# FT2232H.net
KiCad netlist of a schematic drawn in Altium Designer
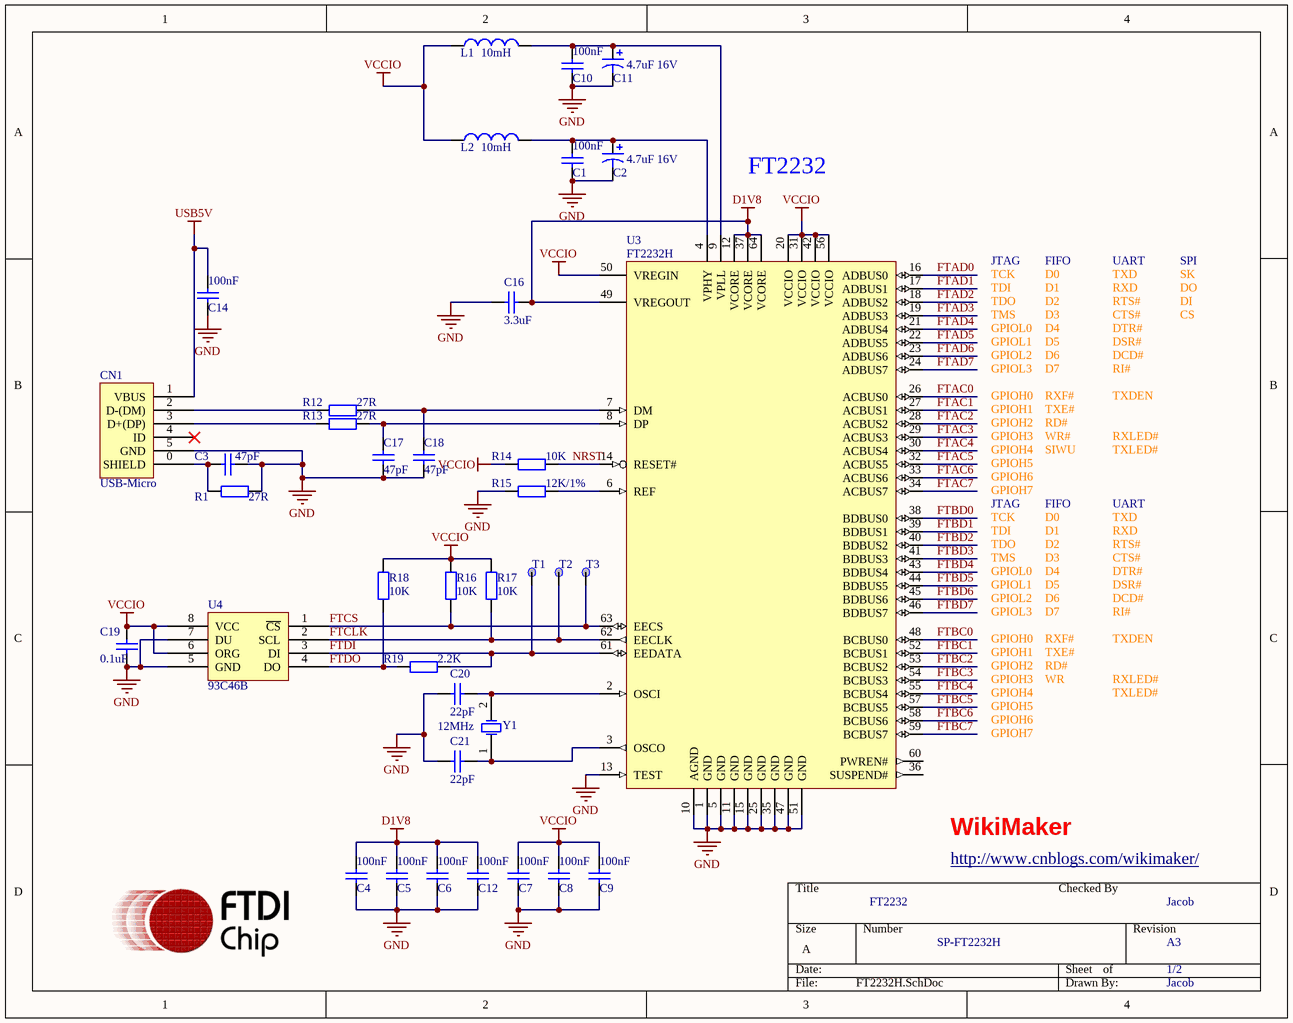
[diagram p0: FT2232H.SchDoc]

(export (version "E")
  (design (tool "Eeschema 10.0.6"))
  (components
    (comp (ref "C1")
      (value "100nF")
      (footprint "0603M")
      (description "Capacitor")
      (fields (field (name "PUBLISHER") "Altium Limited"))
      (libsource (lib "Miscellaneous Devices") (part "Cap"))
    )
    (comp (ref "C2")
      (value "4.7uF 16V")
      (footprint "0805M")
      (description "Polarized Capacitor (Radial)")
      (fields (field (name "PUBLISHER") "Altium Limited"))
      (libsource (lib "Miscellaneous Devices") (part "Cap Pol1"))
    )
    (comp (ref "C3")
      (value "47pF")
      (footprint "0603M")
      (description "Capacitor")
      (fields (field (name "PUBLISHER") "Altium Limited"))
      (libsource (lib "Miscellaneous Devices") (part "Cap"))
    )
    (comp (ref "C4")
      (value "100nF")
      (footprint "0603M")
      (description "Capacitor")
      (fields (field (name "PUBLISHER") "Altium Limited"))
      (libsource (lib "Miscellaneous Devices") (part "Cap"))
    )
    (comp (ref "C5")
      (value "100nF")
      (footprint "0603M")
      (description "Capacitor")
      (fields (field (name "PUBLISHER") "Altium Limited"))
      (libsource (lib "Miscellaneous Devices") (part "Cap"))
    )
    (comp (ref "C6")
      (value "100nF")
      (footprint "0603M")
      (description "Capacitor")
      (fields (field (name "PUBLISHER") "Altium Limited"))
      (libsource (lib "Miscellaneous Devices") (part "Cap"))
    )
    (comp (ref "C7")
      (value "100nF")
      (footprint "0603M")
      (description "Capacitor")
      (fields (field (name "PUBLISHER") "Altium Limited"))
      (libsource (lib "Miscellaneous Devices") (part "Cap"))
    )
    (comp (ref "C8")
      (value "100nF")
      (footprint "0603M")
      (description "Capacitor")
      (fields (field (name "PUBLISHER") "Altium Limited"))
      (libsource (lib "Miscellaneous Devices") (part "Cap"))
    )
    (comp (ref "C9")
      (value "100nF")
      (footprint "0603M")
      (description "Capacitor")
      (fields (field (name "PUBLISHER") "Altium Limited"))
      (libsource (lib "Miscellaneous Devices") (part "Cap"))
    )
    (comp (ref "C10")
      (value "100nF")
      (footprint "0603M")
      (description "Capacitor")
      (fields (field (name "PUBLISHER") "Altium Limited"))
      (libsource (lib "Miscellaneous Devices") (part "Cap"))
    )
    (comp (ref "C11")
      (value "4.7uF 16V")
      (footprint "0805M")
      (description "Polarized Capacitor (Radial)")
      (fields (field (name "PUBLISHER") "Altium Limited"))
      (libsource (lib "Miscellaneous Devices") (part "Cap Pol1"))
    )
    (comp (ref "C12")
      (value "100nF")
      (footprint "0603M")
      (description "Capacitor")
      (fields (field (name "PUBLISHER") "Altium Limited"))
      (libsource (lib "Miscellaneous Devices") (part "Cap"))
    )
    (comp (ref "C14")
      (value "100nF")
      (footprint "0603M")
      (description "Capacitor")
      (fields (field (name "PUBLISHER") "Altium Limited"))
      (libsource (lib "Miscellaneous Devices") (part "Cap"))
    )
    (comp (ref "C16")
      (value "3.3uF")
      (footprint "0805M")
      (description "Capacitor")
      (fields (field (name "PUBLISHER") "Altium Limited"))
      (libsource (lib "Miscellaneous Devices") (part "Cap"))
    )
    (comp (ref "C17")
      (value "47pF")
      (footprint "0603M")
      (description "Capacitor")
      (fields (field (name "PUBLISHER") "Altium Limited"))
      (libsource (lib "Miscellaneous Devices") (part "Cap"))
    )
    (comp (ref "C18")
      (value "47pF")
      (footprint "0603M")
      (description "Capacitor")
      (fields (field (name "PUBLISHER") "Altium Limited"))
      (libsource (lib "Miscellaneous Devices") (part "Cap"))
    )
    (comp (ref "C19")
      (value "0.1uF")
      (footprint "0603M")
      (description "Capacitor")
      (fields (field (name "PUBLISHER") "Altium Limited"))
      (libsource (lib "Miscellaneous Devices") (part "Cap"))
    )
    (comp (ref "C20")
      (value "22pF")
      (footprint "0603M")
      (description "Capacitor")
      (fields (field (name "PUBLISHER") "Altium Limited"))
      (libsource (lib "Miscellaneous Devices") (part "Cap"))
    )
    (comp (ref "C21")
      (value "22pF")
      (footprint "0603M")
      (description "Capacitor")
      (fields (field (name "PUBLISHER") "Altium Limited"))
      (libsource (lib "Miscellaneous Devices") (part "Cap"))
    )
    (comp (ref "CN1")
      (value "USB-Micro")
      (footprint "USB-MICRO-Lite")
      (libsource (lib "Connector") (part "USB-Micro"))
    )
    (comp (ref "L1")
      (value "10mH")
      (footprint "0805M")
      (description "Inductor")
      (fields (field (name "PUBLISHER") "Altium Limited"))
      (libsource (lib "Miscellaneous Devices") (part "Inductor"))
    )
    (comp (ref "L2")
      (value "10mH")
      (footprint "0805M")
      (description "Inductor")
      (fields (field (name "PUBLISHER") "Altium Limited"))
      (libsource (lib "Miscellaneous Devices") (part "Inductor"))
    )
    (comp (ref "R1")
      (value "27R")
      (footprint "0603M")
      (description "Resistor")
      (fields (field (name "PUBLISHER") "Altium Limited"))
      (libsource (lib "") (part "Res2_1"))
    )
    (comp (ref "R12")
      (value "27R")
      (footprint "0603M")
      (description "Resistor")
      (fields (field (name "PUBLISHER") "Altium Limited"))
      (libsource (lib "") (part "Res2_1"))
    )
    (comp (ref "R13")
      (value "27R")
      (footprint "0603M")
      (description "Resistor")
      (fields (field (name "PUBLISHER") "Altium Limited"))
      (libsource (lib "") (part "Res2_1"))
    )
    (comp (ref "R14")
      (value "10K")
      (footprint "0603M")
      (description "Resistor")
      (fields (field (name "PUBLISHER") "Altium Limited"))
      (libsource (lib "") (part "Res2_1"))
    )
    (comp (ref "R15")
      (value "12K/1%")
      (footprint "0603M")
      (description "Resistor")
      (fields (field (name "PUBLISHER") "Altium Limited"))
      (libsource (lib "") (part "Res2_1"))
    )
    (comp (ref "R16")
      (value "10K")
      (footprint "0603M")
      (description "Resistor")
      (fields (field (name "PUBLISHER") "Altium Limited"))
      (libsource (lib "Miscellaneous Devices") (part "Res2"))
    )
    (comp (ref "R17")
      (value "10K")
      (footprint "0603M")
      (description "Resistor")
      (fields (field (name "PUBLISHER") "Altium Limited"))
      (libsource (lib "Miscellaneous Devices") (part "Res2"))
    )
    (comp (ref "R18")
      (value "10K")
      (footprint "0603M")
      (description "Resistor")
      (fields (field (name "PUBLISHER") "Altium Limited"))
      (libsource (lib "Miscellaneous Devices") (part "Res2"))
    )
    (comp (ref "R19")
      (value "2.2K")
      (footprint "0603M")
      (description "Resistor")
      (fields (field (name "PUBLISHER") "Altium Limited"))
      (libsource (lib "") (part "Res2_1"))
    )
    (comp (ref "T1")
      (value "TP")
      (footprint "TP-HOLE")
      (description "Test Point")
      (libsource (lib "Studio") (part "TP"))
    )
    (comp (ref "T2")
      (value "TP")
      (footprint "TP-HOLE")
      (description "Test Point")
      (libsource (lib "Studio") (part "TP"))
    )
    (comp (ref "T3")
      (value "TP")
      (footprint "TP-HOLE")
      (description "Test Point")
      (libsource (lib "Studio") (part "TP"))
    )
    (comp (ref "U3")
      (value "FT2232H")
      (footprint "LQFP-64_N")
      (description "Dual High Speed USB To Multipurpose UART/FIFO IC, LQFP-64, Tape and Reel")
      (fields (field (name "PUBLISHER") "Altium Limited"))
      (libsource (lib "FTDI Communication UART") (part "FT2232HL-Reel"))
    )
    (comp (ref "U4")
      (value "93C46B")
      (footprint "SO8_L")
      (description "1K Microwire Compatible Serial EEPROM")
      (libsource (lib "Studio") (part "93C46B"))
    )
    (comp (ref "Y1")
      (value "12MHz")
      (footprint "XTAL_socket")
      (description "Crystal Oscillator")
      (fields (field (name "PUBLISHER") "Altium Limited"))
      (libsource (lib "Miscellaneous Devices") (part "XTAL"))
    )
  )
  (nets
    (net (code "1") (name "/FTAC0") (class "Default")
      (node (ref "U3") (pin "26") (pinfunction "ACBUS0_26") (pintype "bidirectional"))
    )
    (net (code "2") (name "/FTAC1") (class "Default")
      (node (ref "U3") (pin "27") (pinfunction "ACBUS1_27") (pintype "bidirectional"))
    )
    (net (code "3") (name "/FTAC2") (class "Default")
      (node (ref "U3") (pin "28") (pinfunction "ACBUS2_28") (pintype "bidirectional"))
    )
    (net (code "4") (name "/FTAC3") (class "Default")
      (node (ref "U3") (pin "29") (pinfunction "ACBUS3_29") (pintype "bidirectional"))
    )
    (net (code "5") (name "/FTAC4") (class "Default")
      (node (ref "U3") (pin "30") (pinfunction "ACBUS4_30") (pintype "bidirectional"))
    )
    (net (code "6") (name "/FTAC5") (class "Default")
      (node (ref "U3") (pin "32") (pinfunction "ACBUS5_32") (pintype "bidirectional"))
    )
    (net (code "7") (name "/FTAC6") (class "Default")
      (node (ref "U3") (pin "33") (pinfunction "ACBUS6_33") (pintype "bidirectional"))
    )
    (net (code "8") (name "/FTAC7") (class "Default")
      (node (ref "U3") (pin "34") (pinfunction "ACBUS7_34") (pintype "bidirectional"))
    )
    (net (code "9") (name "/FTAD0") (class "Default")
      (node (ref "U3") (pin "16") (pinfunction "ADBUS0_16") (pintype "bidirectional"))
    )
    (net (code "10") (name "/FTAD1") (class "Default")
      (node (ref "U3") (pin "17") (pinfunction "ADBUS1_17") (pintype "bidirectional"))
    )
    (net (code "11") (name "/FTAD2") (class "Default")
      (node (ref "U3") (pin "18") (pinfunction "ADBUS2_18") (pintype "bidirectional"))
    )
    (net (code "12") (name "/FTAD3") (class "Default")
      (node (ref "U3") (pin "19") (pinfunction "ADBUS3_19") (pintype "bidirectional"))
    )
    (net (code "13") (name "/FTAD4") (class "Default")
      (node (ref "U3") (pin "21") (pinfunction "ADBUS4_21") (pintype "bidirectional"))
    )
    (net (code "14") (name "/FTAD5") (class "Default")
      (node (ref "U3") (pin "22") (pinfunction "ADBUS5_22") (pintype "bidirectional"))
    )
    (net (code "15") (name "/FTAD6") (class "Default")
      (node (ref "U3") (pin "23") (pinfunction "ADBUS6_23") (pintype "bidirectional"))
    )
    (net (code "16") (name "/FTAD7") (class "Default")
      (node (ref "U3") (pin "24") (pinfunction "ADBUS7_24") (pintype "bidirectional"))
    )
    (net (code "17") (name "/FTBC0") (class "Default")
      (node (ref "U3") (pin "48") (pinfunction "BCBUS0_48") (pintype "bidirectional"))
    )
    (net (code "18") (name "/FTBC1") (class "Default")
      (node (ref "U3") (pin "52") (pinfunction "BCBUS1_52") (pintype "bidirectional"))
    )
    (net (code "19") (name "/FTBC2") (class "Default")
      (node (ref "U3") (pin "53") (pinfunction "BCBUS2_53") (pintype "bidirectional"))
    )
    (net (code "20") (name "/FTBC3") (class "Default")
      (node (ref "U3") (pin "54") (pinfunction "BCBUS3_54") (pintype "bidirectional"))
    )
    (net (code "21") (name "/FTBC4") (class "Default")
      (node (ref "U3") (pin "55") (pinfunction "BCBUS4_55") (pintype "bidirectional"))
    )
    (net (code "22") (name "/FTBC5") (class "Default")
      (node (ref "U3") (pin "57") (pinfunction "BCBUS5_57") (pintype "bidirectional"))
    )
    (net (code "23") (name "/FTBC6") (class "Default")
      (node (ref "U3") (pin "58") (pinfunction "BCBUS6_58") (pintype "bidirectional"))
    )
    (net (code "24") (name "/FTBC7") (class "Default")
      (node (ref "U3") (pin "59") (pinfunction "BCBUS7_59") (pintype "bidirectional"))
    )
    (net (code "25") (name "/FTBD0") (class "Default")
      (node (ref "U3") (pin "38") (pinfunction "BDBUS0_38") (pintype "bidirectional"))
    )
    (net (code "26") (name "/FTBD1") (class "Default")
      (node (ref "U3") (pin "39") (pinfunction "BDBUS1_39") (pintype "bidirectional"))
    )
    (net (code "27") (name "/FTBD2") (class "Default")
      (node (ref "U3") (pin "40") (pinfunction "BDBUS2_40") (pintype "bidirectional"))
    )
    (net (code "28") (name "/FTBD3") (class "Default")
      (node (ref "U3") (pin "41") (pinfunction "BDBUS3_41") (pintype "bidirectional"))
    )
    (net (code "29") (name "/FTBD4") (class "Default")
      (node (ref "U3") (pin "43") (pinfunction "BDBUS4_43") (pintype "bidirectional"))
    )
    (net (code "30") (name "/FTBD5") (class "Default")
      (node (ref "U3") (pin "44") (pinfunction "BDBUS5_44") (pintype "bidirectional"))
    )
    (net (code "31") (name "/FTBD6") (class "Default")
      (node (ref "U3") (pin "45") (pinfunction "BDBUS6_45") (pintype "bidirectional"))
    )
    (net (code "32") (name "/FTBD7") (class "Default")
      (node (ref "U3") (pin "46") (pinfunction "BDBUS7_46") (pintype "bidirectional"))
    )
    (net (code "33") (name "/FTCLK") (class "Default")
      (node (ref "R17") (pin "2") (pinfunction "2_2") (pintype "passive"))
      (node (ref "T2") (pin "1") (pinfunction "1_1") (pintype "passive"))
      (node (ref "U3") (pin "62") (pinfunction "EECLK_62") (pintype "output"))
      (node (ref "U4") (pin "2") (pinfunction "SCL_2") (pintype "passive"))
    )
    (net (code "34") (name "/FTCS") (class "Default")
      (node (ref "R16") (pin "2") (pinfunction "2_2") (pintype "passive"))
      (node (ref "T3") (pin "1") (pinfunction "1_1") (pintype "passive"))
      (node (ref "U3") (pin "63") (pinfunction "EECS_63") (pintype "bidirectional"))
      (node (ref "U4") (pin "1") (pinfunction "~{CS}_1") (pintype "passive"))
    )
    (net (code "35") (name "/FTDI") (class "Default")
      (node (ref "R19") (pin "1") (pinfunction "1_1") (pintype "passive"))
      (node (ref "T1") (pin "1") (pinfunction "1_1") (pintype "passive"))
      (node (ref "U3") (pin "61") (pinfunction "EEDATA_61") (pintype "bidirectional"))
      (node (ref "U4") (pin "3") (pinfunction "DI_3") (pintype "passive"))
    )
    (net (code "36") (name "/FTDO") (class "Default")
      (node (ref "R18") (pin "2") (pinfunction "2_2") (pintype "passive"))
      (node (ref "R19") (pin "2") (pinfunction "2_2") (pintype "passive"))
      (node (ref "U4") (pin "4") (pinfunction "DO_4") (pintype "passive"))
    )
    (net (code "37") (name "/NRST") (class "Default")
      (node (ref "R14") (pin "1") (pinfunction "1_1") (pintype "passive"))
      (node (ref "U3") (pin "14") (pinfunction "RESET#_14") (pintype "input"))
    )
    (net (code "38") (name "D1V8") (class "Default")
      (node (ref "C12") (pin "2") (pinfunction "2_2") (pintype "passive"))
      (node (ref "C16") (pin "1") (pinfunction "1_1") (pintype "passive"))
      (node (ref "C4") (pin "2") (pinfunction "2_2") (pintype "passive"))
      (node (ref "C5") (pin "2") (pinfunction "2_2") (pintype "passive"))
      (node (ref "C6") (pin "2") (pinfunction "2_2") (pintype "passive"))
      (node (ref "U3") (pin "12") (pinfunction "VCORE_12") (pintype "power_in"))
      (node (ref "U3") (pin "37") (pinfunction "VCORE_37") (pintype "power_in"))
      (node (ref "U3") (pin "49") (pinfunction "VREGOUT_49") (pintype "power_in"))
      (node (ref "U3") (pin "64") (pinfunction "VCORE_64") (pintype "power_in"))
    )
    (net (code "39") (name "GND") (class "Default")
      (node (ref "C1") (pin "1") (pinfunction "1_1") (pintype "passive"))
      (node (ref "C10") (pin "1") (pinfunction "1_1") (pintype "passive"))
      (node (ref "C11") (pin "2") (pinfunction "2_2") (pintype "passive"))
      (node (ref "C12") (pin "1") (pinfunction "1_1") (pintype "passive"))
      (node (ref "C14") (pin "1") (pinfunction "1_1") (pintype "passive"))
      (node (ref "C16") (pin "2") (pinfunction "2_2") (pintype "passive"))
      (node (ref "C17") (pin "1") (pinfunction "1_1") (pintype "passive"))
      (node (ref "C18") (pin "1") (pinfunction "1_1") (pintype "passive"))
      (node (ref "C19") (pin "2") (pinfunction "2_2") (pintype "passive"))
      (node (ref "C2") (pin "2") (pinfunction "2_2") (pintype "passive"))
      (node (ref "C20") (pin "1") (pinfunction "1_1") (pintype "passive"))
      (node (ref "C21") (pin "1") (pinfunction "1_1") (pintype "passive"))
      (node (ref "C3") (pin "2") (pinfunction "2_2") (pintype "passive"))
      (node (ref "C4") (pin "1") (pinfunction "1_1") (pintype "passive"))
      (node (ref "C5") (pin "1") (pinfunction "1_1") (pintype "passive"))
      (node (ref "C6") (pin "1") (pinfunction "1_1") (pintype "passive"))
      (node (ref "C7") (pin "1") (pinfunction "1_1") (pintype "passive"))
      (node (ref "C8") (pin "1") (pinfunction "1_1") (pintype "passive"))
      (node (ref "C9") (pin "1") (pinfunction "1_1") (pintype "passive"))
      (node (ref "CN1") (pin "5") (pinfunction "GND_5") (pintype "passive"))
      (node (ref "R1") (pin "1") (pinfunction "1_1") (pintype "passive"))
      (node (ref "R15") (pin "2") (pinfunction "2_2") (pintype "passive"))
      (node (ref "U3") (pin "1") (pinfunction "GND_1") (pintype "power_in"))
      (node (ref "U3") (pin "10") (pinfunction "AGND_10") (pintype "power_in"))
      (node (ref "U3") (pin "11") (pinfunction "GND_11") (pintype "power_in"))
      (node (ref "U3") (pin "13") (pinfunction "TEST_13") (pintype "input"))
      (node (ref "U3") (pin "15") (pinfunction "GND_15") (pintype "power_in"))
      (node (ref "U3") (pin "25") (pinfunction "GND_25") (pintype "power_in"))
      (node (ref "U3") (pin "35") (pinfunction "GND_35") (pintype "power_in"))
      (node (ref "U3") (pin "47") (pinfunction "GND_47") (pintype "power_in"))
      (node (ref "U3") (pin "5") (pinfunction "GND_5") (pintype "power_in"))
      (node (ref "U3") (pin "51") (pinfunction "GND_51") (pintype "power_in"))
      (node (ref "U4") (pin "5") (pinfunction "GND_5") (pintype "passive"))
      (node (ref "U4") (pin "7") (pinfunction "DU_7") (pintype "passive"))
    )
    (net (code "40") (name "Net-(CN1-D+(DP))") (class "Default")
      (node (ref "CN1") (pin "3") (pinfunction "D+(DP)_3") (pintype "passive"))
      (node (ref "R13") (pin "2") (pinfunction "2_2") (pintype "passive"))
    )
    (net (code "41") (name "Net-(CN1-D-(DM))") (class "Default")
      (node (ref "CN1") (pin "2") (pinfunction "D-(DM)_2") (pintype "passive"))
      (node (ref "R12") (pin "2") (pinfunction "2_2") (pintype "passive"))
    )
    (net (code "42") (name "Net-(CN1-SHIELD)") (class "Default")
      (node (ref "C3") (pin "1") (pinfunction "1_1") (pintype "passive"))
      (node (ref "CN1") (pin "0") (pinfunction "SHIELD_0") (pintype "passive"))
      (node (ref "R1") (pin "2") (pinfunction "2_2") (pintype "passive"))
    )
    (net (code "43") (name "Net-(U3-DM)") (class "Default")
      (node (ref "C18") (pin "2") (pinfunction "2_2") (pintype "passive"))
      (node (ref "R12") (pin "1") (pinfunction "1_1") (pintype "passive"))
      (node (ref "U3") (pin "7") (pinfunction "DM_7") (pintype "input"))
    )
    (net (code "44") (name "Net-(U3-DP)") (class "Default")
      (node (ref "C17") (pin "2") (pinfunction "2_2") (pintype "passive"))
      (node (ref "R13") (pin "1") (pinfunction "1_1") (pintype "passive"))
      (node (ref "U3") (pin "8") (pinfunction "DP_8") (pintype "input"))
    )
    (net (code "45") (name "Net-(U3-OSCI)") (class "Default")
      (node (ref "C20") (pin "2") (pinfunction "2_2") (pintype "passive"))
      (node (ref "U3") (pin "2") (pinfunction "OSCI_2") (pintype "input"))
      (node (ref "Y1") (pin "2") (pinfunction "OSC2_2") (pintype "passive"))
    )
    (net (code "46") (name "Net-(U3-OSCO)") (class "Default")
      (node (ref "C21") (pin "2") (pinfunction "2_2") (pintype "passive"))
      (node (ref "U3") (pin "3") (pinfunction "OSCO_3") (pintype "output"))
      (node (ref "Y1") (pin "1") (pinfunction "OSC1_1") (pintype "passive"))
    )
    (net (code "47") (name "Net-(U3-REF)") (class "Default")
      (node (ref "R15") (pin "1") (pinfunction "1_1") (pintype "passive"))
      (node (ref "U3") (pin "6") (pinfunction "REF_6") (pintype "input"))
    )
    (net (code "48") (name "Net-(U3-VPHY)") (class "Default")
      (node (ref "C1") (pin "2") (pinfunction "2_2") (pintype "passive"))
      (node (ref "C2") (pin "1") (pinfunction "1_1") (pintype "passive"))
      (node (ref "L2") (pin "2") (pinfunction "2_2") (pintype "passive"))
      (node (ref "U3") (pin "4") (pinfunction "VPHY_4") (pintype "power_in"))
    )
    (net (code "49") (name "Net-(U3-VPLL)") (class "Default")
      (node (ref "C10") (pin "2") (pinfunction "2_2") (pintype "passive"))
      (node (ref "C11") (pin "1") (pinfunction "1_1") (pintype "passive"))
      (node (ref "L1") (pin "2") (pinfunction "2_2") (pintype "passive"))
      (node (ref "U3") (pin "9") (pinfunction "VPLL_9") (pintype "power_in"))
    )
    (net (code "50") (name "USB5V") (class "Default")
      (node (ref "C14") (pin "2") (pinfunction "2_2") (pintype "passive"))
      (node (ref "CN1") (pin "1") (pinfunction "VBUS_1") (pintype "passive"))
    )
    (net (code "51") (name "VCCIO") (class "Default")
      (node (ref "C19") (pin "1") (pinfunction "1_1") (pintype "passive"))
      (node (ref "C7") (pin "2") (pinfunction "2_2") (pintype "passive"))
      (node (ref "C8") (pin "2") (pinfunction "2_2") (pintype "passive"))
      (node (ref "C9") (pin "2") (pinfunction "2_2") (pintype "passive"))
      (node (ref "L1") (pin "1") (pinfunction "1_1") (pintype "passive"))
      (node (ref "L2") (pin "1") (pinfunction "1_1") (pintype "passive"))
      (node (ref "R14") (pin "2") (pinfunction "2_2") (pintype "passive"))
      (node (ref "R16") (pin "1") (pinfunction "1_1") (pintype "passive"))
      (node (ref "R17") (pin "1") (pinfunction "1_1") (pintype "passive"))
      (node (ref "R18") (pin "1") (pinfunction "1_1") (pintype "passive"))
      (node (ref "U3") (pin "20") (pinfunction "VCCIO_20") (pintype "power_in"))
      (node (ref "U3") (pin "31") (pinfunction "VCCIO_31") (pintype "power_in"))
      (node (ref "U3") (pin "42") (pinfunction "VCCIO_42") (pintype "power_in"))
      (node (ref "U3") (pin "50") (pinfunction "VREGIN_50") (pintype "power_in"))
      (node (ref "U3") (pin "56") (pinfunction "VCCIO_56") (pintype "power_in"))
      (node (ref "U4") (pin "6") (pinfunction "ORG_6") (pintype "passive"))
      (node (ref "U4") (pin "8") (pinfunction "VCC_8") (pintype "passive"))
    )
    (net (code "52") (name "unconnected-(CN1-ID-Pad4)") (class "Default")
      (node (ref "CN1") (pin "4") (pinfunction "ID_4") (pintype "passive+no_connect"))
    )
    (net (code "53") (name "unconnected-(U3-PWREN#-Pad60)") (class "Default")
      (node (ref "U3") (pin "60") (pinfunction "PWREN#_60") (pintype "output"))
    )
    (net (code "54") (name "unconnected-(U3-SUSPEND#-Pad36)") (class "Default")
      (node (ref "U3") (pin "36") (pinfunction "SUSPEND#_36") (pintype "output"))
    )
  )
)
